# IO_extender.net
KiCad netlist of a schematic drawn in Altium Designer
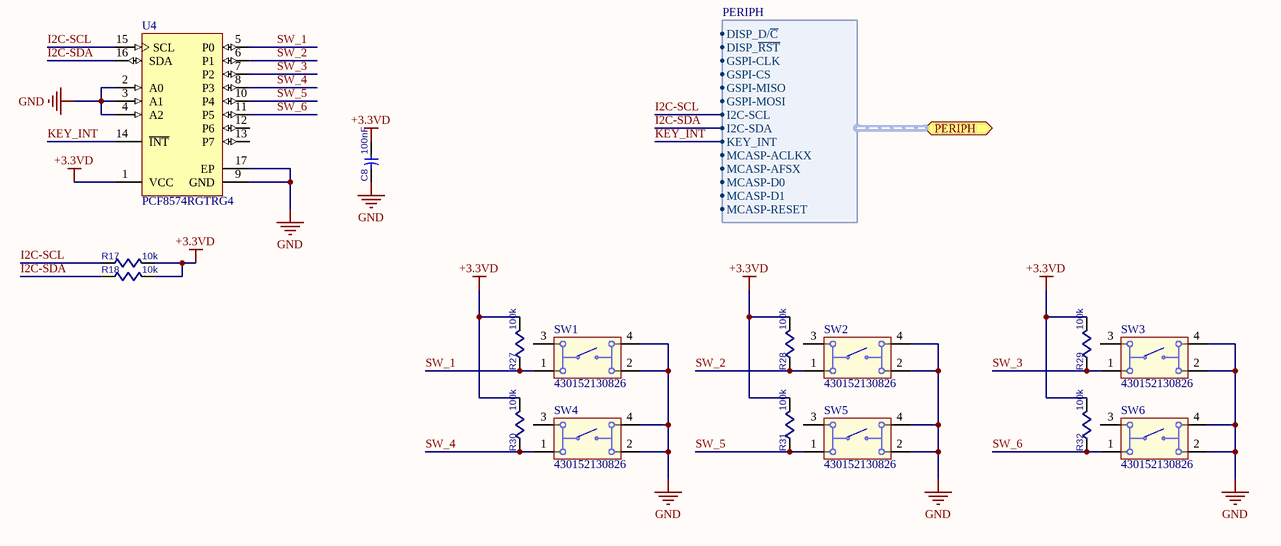
[diagram p0: IO_extender.SchDoc]

(export (version "E")
  (design (tool "Eeschema 10.0.6"))
  (components
    (comp (ref "C8") (value "100nF") (footprint "C_0603A") (libsource (lib "WiFi_3200") (part "C_0603")))
    (comp (ref "R17") (value "10k") (footprint "R_0603") (libsource (lib "WiFi_3200") (part "R_0603")))
    (comp (ref "R18") (value "10k") (footprint "R_0603") (libsource (lib "WiFi_3200") (part "R_0603")))
    (comp (ref "R27") (value "100k") (footprint "R_0603") (libsource (lib "WiFi_3200") (part "R_0603")))
    (comp (ref "R28") (value "100k") (footprint "R_0603") (libsource (lib "WiFi_3200") (part "R_0603")))
    (comp (ref "R29") (value "100k") (footprint "R_0603") (libsource (lib "WiFi_3200") (part "R_0603")))
    (comp (ref "R30") (value "100k") (footprint "R_0603") (libsource (lib "WiFi_3200") (part "R_0603")))
    (comp (ref "R31") (value "100k") (footprint "R_0603") (libsource (lib "WiFi_3200") (part "R_0603")))
    (comp (ref "R32") (value "100k") (footprint "R_0603") (libsource (lib "WiFi_3200") (part "R_0603")))
    (comp (ref "SW1")
      (value "430152130826")
      (footprint "430152130826")
      (description "WS-TASV SMD Tact Switch 6X6 mm")
      (fields (field (name "MANUFACTURER") "Wuerth Elektronik"))
      (libsource (lib "Altium Content Vault") (part "WE-TACT-SW-4"))
    )
    (comp (ref "SW2")
      (value "430152130826")
      (footprint "430152130826")
      (description "WS-TASV SMD Tact Switch 6X6 mm")
      (fields (field (name "MANUFACTURER") "Wuerth Elektronik"))
      (libsource (lib "Altium Content Vault") (part "WE-TACT-SW-4"))
    )
    (comp (ref "SW3")
      (value "430152130826")
      (footprint "430152130826")
      (description "WS-TASV SMD Tact Switch 6X6 mm")
      (fields (field (name "MANUFACTURER") "Wuerth Elektronik"))
      (libsource (lib "Altium Content Vault") (part "WE-TACT-SW-4"))
    )
    (comp (ref "SW4")
      (value "430152130826")
      (footprint "430152130826")
      (description "WS-TASV SMD Tact Switch 6X6 mm")
      (fields (field (name "MANUFACTURER") "Wuerth Elektronik"))
      (libsource (lib "Altium Content Vault") (part "WE-TACT-SW-4"))
    )
    (comp (ref "SW5")
      (value "430152130826")
      (footprint "430152130826")
      (description "WS-TASV SMD Tact Switch 6X6 mm")
      (fields (field (name "MANUFACTURER") "Wuerth Elektronik"))
      (libsource (lib "Altium Content Vault") (part "WE-TACT-SW-4"))
    )
    (comp (ref "SW6")
      (value "430152130826")
      (footprint "430152130826")
      (description "WS-TASV SMD Tact Switch 6X6 mm")
      (fields (field (name "MANUFACTURER") "Wuerth Elektronik"))
      (libsource (lib "Altium Content Vault") (part "WE-TACT-SW-4"))
    )
    (comp (ref "U4")
      (value "PCF8574RGTRG4")
      (footprint "RGT16-1600X1600TP")
      (fields (field (name "MANUFACTURER") "Texas Instruments"))
      (libsource (lib "Altium Content Vault") (part "TI-PCF8574-QFN_RGT-16"))
    )
  )
  (nets
    (net (code "2") (name "+3.3VD") (class "Default")
      (node (ref "C8") (pin "1") (pinfunction "1_1") (pintype "passive"))
      (node (ref "R17") (pin "1") (pinfunction "1_1") (pintype "passive"))
      (node (ref "R18") (pin "1") (pinfunction "1_1") (pintype "passive"))
      (node (ref "R27") (pin "1") (pinfunction "1_1") (pintype "passive"))
      (node (ref "R28") (pin "1") (pinfunction "1_1") (pintype "passive"))
      (node (ref "R29") (pin "1") (pinfunction "1_1") (pintype "passive"))
      (node (ref "R30") (pin "1") (pinfunction "1_1") (pintype "passive"))
      (node (ref "R31") (pin "1") (pinfunction "1_1") (pintype "passive"))
      (node (ref "R32") (pin "1") (pinfunction "1_1") (pintype "passive"))
      (node (ref "U4") (pin "1") (pinfunction "VCC_1") (pintype "power_in"))
    )
    (net (code "3") (name "/I2C-SCL") (class "Default")
      (node (ref "R17") (pin "2") (pinfunction "2_2") (pintype "passive"))
      (node (ref "U4") (pin "15") (pinfunction "SCL_15") (pintype "input"))
    )
    (net (code "4") (name "/I2C-SDA") (class "Default")
      (node (ref "R18") (pin "2") (pinfunction "2_2") (pintype "passive"))
      (node (ref "U4") (pin "16") (pinfunction "SDA_16") (pintype "bidirectional"))
    )
    (net (code "5") (name "/KEY_INT") (class "Default")
      (node (ref "U4") (pin "14") (pinfunction "~{INT}_14") (pintype "open_collector"))
    )
    (net (code "6") (name "/SW_1") (class "Default")
      (node (ref "R27") (pin "2") (pinfunction "2_2") (pintype "passive"))
      (node (ref "SW1") (pin "1") (pinfunction "1_1") (pintype "passive"))
      (node (ref "U4") (pin "5") (pinfunction "P0_5") (pintype "bidirectional"))
    )
    (net (code "7") (name "/SW_2") (class "Default")
      (node (ref "R28") (pin "2") (pinfunction "2_2") (pintype "passive"))
      (node (ref "SW2") (pin "1") (pinfunction "1_1") (pintype "passive"))
      (node (ref "U4") (pin "6") (pinfunction "P1_6") (pintype "bidirectional"))
    )
    (net (code "8") (name "/SW_3") (class "Default")
      (node (ref "R29") (pin "2") (pinfunction "2_2") (pintype "passive"))
      (node (ref "SW3") (pin "1") (pinfunction "1_1") (pintype "passive"))
      (node (ref "U4") (pin "7") (pinfunction "P2_7") (pintype "bidirectional"))
    )
    (net (code "9") (name "/SW_4") (class "Default")
      (node (ref "R30") (pin "2") (pinfunction "2_2") (pintype "passive"))
      (node (ref "SW4") (pin "1") (pinfunction "1_1") (pintype "passive"))
      (node (ref "U4") (pin "8") (pinfunction "P3_8") (pintype "bidirectional"))
    )
    (net (code "10") (name "/SW_5") (class "Default")
      (node (ref "R31") (pin "2") (pinfunction "2_2") (pintype "passive"))
      (node (ref "SW5") (pin "1") (pinfunction "1_1") (pintype "passive"))
      (node (ref "U4") (pin "10") (pinfunction "P4_10") (pintype "bidirectional"))
    )
    (net (code "11") (name "/SW_6") (class "Default")
      (node (ref "R32") (pin "2") (pinfunction "2_2") (pintype "passive"))
      (node (ref "SW6") (pin "1") (pinfunction "1_1") (pintype "passive"))
      (node (ref "U4") (pin "11") (pinfunction "P5_11") (pintype "bidirectional"))
    )
    (net (code "13") (name "GND") (class "Default")
      (node (ref "C8") (pin "2") (pinfunction "2_2") (pintype "passive"))
      (node (ref "SW1") (pin "2") (pinfunction "2_2") (pintype "passive"))
      (node (ref "SW1") (pin "4") (pinfunction "4_4") (pintype "passive"))
      (node (ref "SW2") (pin "2") (pinfunction "2_2") (pintype "passive"))
      (node (ref "SW2") (pin "4") (pinfunction "4_4") (pintype "passive"))
      (node (ref "SW3") (pin "2") (pinfunction "2_2") (pintype "passive"))
      (node (ref "SW3") (pin "4") (pinfunction "4_4") (pintype "passive"))
      (node (ref "SW4") (pin "2") (pinfunction "2_2") (pintype "passive"))
      (node (ref "SW4") (pin "4") (pinfunction "4_4") (pintype "passive"))
      (node (ref "SW5") (pin "2") (pinfunction "2_2") (pintype "passive"))
      (node (ref "SW5") (pin "4") (pinfunction "4_4") (pintype "passive"))
      (node (ref "SW6") (pin "2") (pinfunction "2_2") (pintype "passive"))
      (node (ref "SW6") (pin "4") (pinfunction "4_4") (pintype "passive"))
      (node (ref "U4") (pin "17") (pinfunction "EP_17") (pintype "passive"))
      (node (ref "U4") (pin "2") (pinfunction "A0_2") (pintype "input"))
      (node (ref "U4") (pin "3") (pinfunction "A1_3") (pintype "input"))
      (node (ref "U4") (pin "4") (pinfunction "A2_4") (pintype "input"))
      (node (ref "U4") (pin "9") (pinfunction "GND_9") (pintype "power_in"))
    )
    (net (code "14") (name "unconnected-(SW1-Pad3)") (class "Default")
      (node (ref "SW1") (pin "3") (pinfunction "3_3") (pintype "passive"))
    )
    (net (code "15") (name "unconnected-(SW2-Pad3)") (class "Default")
      (node (ref "SW2") (pin "3") (pinfunction "3_3") (pintype "passive"))
    )
    (net (code "16") (name "unconnected-(SW3-Pad3)") (class "Default")
      (node (ref "SW3") (pin "3") (pinfunction "3_3") (pintype "passive"))
    )
    (net (code "17") (name "unconnected-(SW4-Pad3)") (class "Default")
      (node (ref "SW4") (pin "3") (pinfunction "3_3") (pintype "passive"))
    )
    (net (code "18") (name "unconnected-(SW5-Pad3)") (class "Default")
      (node (ref "SW5") (pin "3") (pinfunction "3_3") (pintype "passive"))
    )
    (net (code "19") (name "unconnected-(SW6-Pad3)") (class "Default")
      (node (ref "SW6") (pin "3") (pinfunction "3_3") (pintype "passive"))
    )
    (net (code "20") (name "unconnected-(U4-P6-Pad12)") (class "Default")
      (node (ref "U4") (pin "12") (pinfunction "P6_12") (pintype "bidirectional"))
    )
    (net (code "21") (name "unconnected-(U4-P7-Pad13)") (class "Default")
      (node (ref "U4") (pin "13") (pinfunction "P7_13") (pintype "bidirectional"))
    )
  )
)
